# 03-PeripheralPart-V2_3.net
KiCad netlist of a schematic drawn in Altium Designer
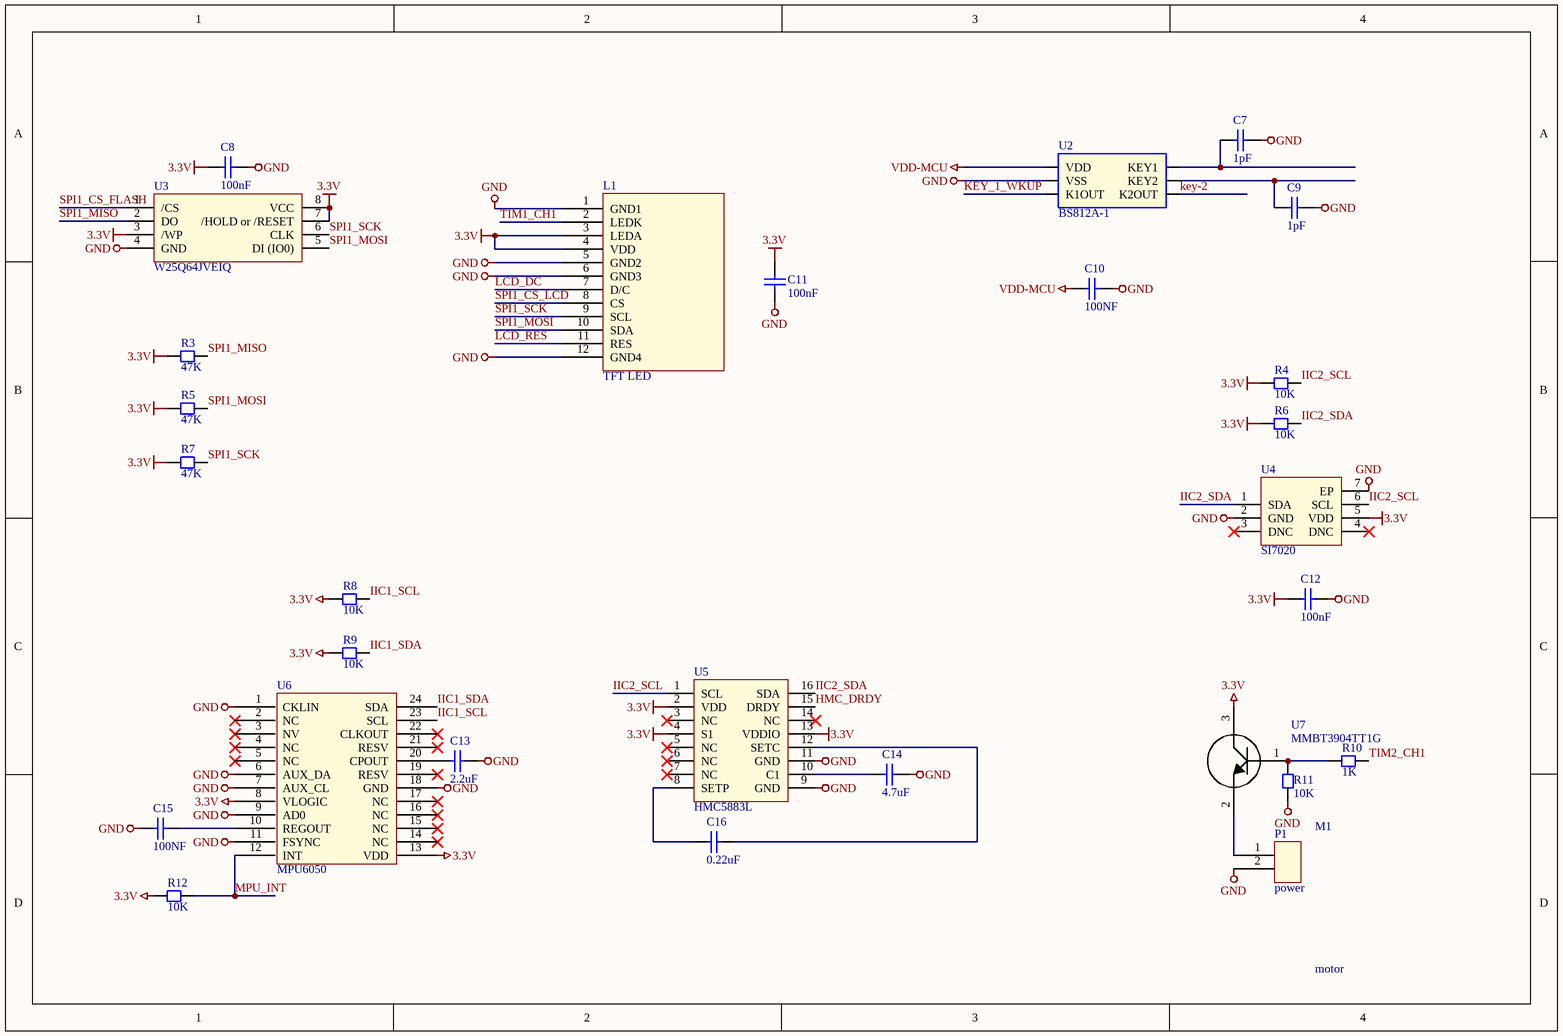
[diagram p0: 03-PeripheralPart-V2.3.SchDoc]

(export (version "E")
  (design (tool "Eeschema 10.0.6"))
  (components
    (comp (ref "C7")
      (value "1pF")
      (footprint "CC1005-0402")
      (description "贴片电容")
      (libsource (lib "tianxiaohua_Schlib") (part "Chip capacitor"))
    )
    (comp (ref "C8")
      (value "100nF")
      (footprint "CC1005-0402")
      (description "贴片电容")
      (libsource (lib "tianxiaohua_Schlib") (part "Chip capacitor"))
    )
    (comp (ref "C9")
      (value "1pF")
      (footprint "CC1005-0402")
      (description "贴片电容")
      (libsource (lib "tianxiaohua_Schlib") (part "Chip capacitor"))
    )
    (comp (ref "C10")
      (value "100NF")
      (footprint "CC1005-0402")
      (description "贴片电容")
      (libsource (lib "tianxiaohua_Schlib") (part "Chip capacitor"))
    )
    (comp (ref "C11")
      (value "100nF")
      (footprint "CC1005-0402")
      (description "贴片电容")
      (libsource (lib "tianxiaohua_Schlib") (part "Chip capacitor"))
    )
    (comp (ref "C12")
      (value "100nF")
      (footprint "CC1005-0402")
      (description "贴片电容")
      (libsource (lib "tianxiaohua_Schlib") (part "Chip capacitor"))
    )
    (comp (ref "C13")
      (value "2.2uF")
      (footprint "CC1005-0402")
      (description "贴片电容")
      (libsource (lib "tianxiaohua_Schlib") (part "Chip capacitor"))
    )
    (comp (ref "C14")
      (value "4.7uF")
      (footprint "CC1005-0402")
      (description "贴片电容")
      (libsource (lib "tianxiaohua_Schlib") (part "Chip capacitor"))
    )
    (comp (ref "C15")
      (value "100NF")
      (footprint "CC1005-0402")
      (description "贴片电容")
      (libsource (lib "tianxiaohua_Schlib") (part "Chip capacitor"))
    )
    (comp (ref "C16")
      (value "0.22uF")
      (footprint "CC1005-0402")
      (description "贴片电容")
      (libsource (lib "tianxiaohua_Schlib") (part "Chip capacitor"))
    )
    (comp (ref "L1")
      (value "TFT LED")
      (footprint "LCD-1.3-(2)")
      (description "1.3寸显示屏幕")
      (libsource (lib "tianxiaohua_Schlib") (part "LCD-IPSscreen-1.3"))
    )
    (comp (ref "M1")
      (value "motor")
      (footprint "motor")
      (description "震动马达")
      (libsource (lib "tianxiaohua_Schlib") (part "motor"))
    )
    (comp (ref "P1")
      (value "power")
      (footprint "POWER-3.7V")
      (libsource (lib "tianxiaohua_Schlib") (part "power"))
    )
    (comp (ref "R3")
      (value "47K")
      (footprint "CR1005-0402")
      (description "贴片电阻")
      (libsource (lib "tianxiaohua_Schlib") (part "Chip resistor"))
    )
    (comp (ref "R4")
      (value "10K")
      (footprint "CR1005-0402")
      (description "贴片电阻")
      (libsource (lib "tianxiaohua_Schlib") (part "Chip resistor"))
    )
    (comp (ref "R5")
      (value "47K")
      (footprint "CR1005-0402")
      (description "贴片电阻")
      (libsource (lib "tianxiaohua_Schlib") (part "Chip resistor"))
    )
    (comp (ref "R6")
      (value "10K")
      (footprint "CR1005-0402")
      (description "贴片电阻")
      (libsource (lib "tianxiaohua_Schlib") (part "Chip resistor"))
    )
    (comp (ref "R7")
      (value "47K")
      (footprint "CR1005-0402")
      (description "贴片电阻")
      (libsource (lib "tianxiaohua_Schlib") (part "Chip resistor"))
    )
    (comp (ref "R8")
      (value "10K")
      (footprint "CR1005-0402")
      (description "贴片电阻")
      (libsource (lib "tianxiaohua_Schlib") (part "Chip resistor"))
    )
    (comp (ref "R9")
      (value "10K")
      (footprint "CR1005-0402")
      (description "贴片电阻")
      (libsource (lib "tianxiaohua_Schlib") (part "Chip resistor"))
    )
    (comp (ref "R10")
      (value "1K")
      (footprint "CR1005-0402")
      (description "贴片电阻")
      (libsource (lib "tianxiaohua_Schlib") (part "Chip resistor"))
    )
    (comp (ref "R11")
      (value "10K")
      (footprint "CR1005-0402")
      (description "贴片电阻")
      (libsource (lib "") (part "Chip resistor_1"))
    )
    (comp (ref "R12")
      (value "10K")
      (footprint "CR1005-0402")
      (description "贴片电阻")
      (libsource (lib "tianxiaohua_Schlib") (part "Chip resistor"))
    )
    (comp (ref "U2")
      (value "BS812A-1")
      (footprint "SOT23-6")
      (description "触摸按键 两路 SOP23-6封装极简电路")
      (libsource (lib "tianxiaohua_Schlib") (part "BS812A-1"))
    )
    (comp (ref "U3")
      (value "W25Q64JVEIQ")
      (footprint "WSON-8_L8.0-W6.10-P1.27-TL-EP")
      (description "FLASH")
      (libsource (lib "tianxiaohua_Schlib") (part "W25Q256JVEIQ"))
    )
    (comp (ref "U4")
      (value "SI7020")
      (footprint "DFN-6")
      (description "温湿度传感器芯片")
      (libsource (lib "tianxiaohua_Schlib") (part "SI7020"))
    )
    (comp (ref "U5")
      (value "HMC5883L")
      (footprint "LPCC-16_L3.0-W3.0-P0.50-BL")
      (description "三轴罗盘")
      (libsource (lib "tianxiaohua_Schlib") (part "HMC5883L"))
    )
    (comp (ref "U6")
      (value "MPU6050")
      (footprint "QFN24 - duplicate")
      (description "陀螺仪")
      (libsource (lib "tianxiaohua_Schlib") (part "MPU6050"))
    )
    (comp (ref "U7")
      (value "MMBT3904TT1G")
      (footprint "SOT-416")
      (description "NPN 电流 - 集电极（Ic）（最大值）：200mA 电压 - 集射极击穿（最大值）：40V SOT-23-3")
      (libsource (lib "tianxiaohua_Schlib") (part "MMBT3904TT1G"))
    )
  )
  (nets
    (net (code "1") (name "/HMC_DRDY") (class "Default")
      (node (ref "U5") (pin "15") (pinfunction "DRDY_15") (pintype "passive"))
    )
    (net (code "2") (name "/IIC1_SCL") (class "Default")
      (node (ref "R8") (pin "1") (pinfunction "1_1") (pintype "passive"))
      (node (ref "U6") (pin "23") (pinfunction "SCL_23") (pintype "passive"))
    )
    (net (code "3") (name "/IIC1_SDA") (class "Default")
      (node (ref "R9") (pin "1") (pinfunction "1_1") (pintype "passive"))
      (node (ref "U6") (pin "24") (pinfunction "SDA_24") (pintype "passive"))
    )
    (net (code "4") (name "/IIC2_SCL") (class "Default")
      (node (ref "R4") (pin "1") (pinfunction "1_1") (pintype "passive"))
      (node (ref "U4") (pin "6") (pinfunction "SCL_6") (pintype "passive"))
      (node (ref "U5") (pin "1") (pinfunction "SCL_1") (pintype "passive"))
    )
    (net (code "5") (name "/IIC2_SDA") (class "Default")
      (node (ref "R6") (pin "1") (pinfunction "1_1") (pintype "passive"))
      (node (ref "U4") (pin "1") (pinfunction "SDA_1") (pintype "passive"))
      (node (ref "U5") (pin "16") (pinfunction "SDA_16") (pintype "passive"))
    )
    (net (code "6") (name "/KEY_1_WKUP") (class "Default")
      (node (ref "U2") (pin "3") (pinfunction "K1OUT_3") (pintype "passive"))
    )
    (net (code "7") (name "/LCD_DC") (class "Default")
      (node (ref "L1") (pin "7") (pinfunction "D/C_7") (pintype "passive"))
    )
    (net (code "8") (name "/LCD_RES") (class "Default")
      (node (ref "L1") (pin "11") (pinfunction "RES_11") (pintype "passive"))
    )
    (net (code "9") (name "/MPU_INT") (class "Default")
      (node (ref "R12") (pin "1") (pinfunction "1_1") (pintype "passive"))
      (node (ref "U6") (pin "12") (pinfunction "INT_12") (pintype "passive"))
    )
    (net (code "10") (name "/SPI1_CS_FLASH") (class "Default")
      (node (ref "U3") (pin "1") (pinfunction "/CS_1") (pintype "passive"))
    )
    (net (code "11") (name "/SPI1_CS_LCD") (class "Default")
      (node (ref "L1") (pin "8") (pinfunction "CS_8") (pintype "passive"))
    )
    (net (code "12") (name "/SPI1_MISO") (class "Default")
      (node (ref "R3") (pin "1") (pinfunction "1_1") (pintype "passive"))
      (node (ref "U3") (pin "2") (pinfunction "DO_2") (pintype "passive"))
    )
    (net (code "13") (name "/SPI1_MOSI") (class "Default")
      (node (ref "L1") (pin "10") (pinfunction "SDA_10") (pintype "passive"))
      (node (ref "R5") (pin "1") (pinfunction "1_1") (pintype "passive"))
      (node (ref "U3") (pin "5") (pinfunction "DI_(IO0)_5") (pintype "passive"))
    )
    (net (code "14") (name "/SPI1_SCK") (class "Default")
      (node (ref "L1") (pin "9") (pinfunction "SCL_9") (pintype "passive"))
      (node (ref "R7") (pin "1") (pinfunction "1_1") (pintype "passive"))
      (node (ref "U3") (pin "6") (pinfunction "CLK_6") (pintype "passive"))
    )
    (net (code "15") (name "/TIM1_CH1") (class "Default")
      (node (ref "L1") (pin "2") (pinfunction "LEDK_2") (pintype "passive"))
    )
    (net (code "16") (name "/TIM2_CH1") (class "Default")
      (node (ref "R10") (pin "1") (pinfunction "1_1") (pintype "passive"))
    )
    (net (code "17") (name "/key-2") (class "Default")
      (node (ref "U2") (pin "4") (pinfunction "K2OUT_4") (pintype "passive"))
    )
    (net (code "18") (name "3.3V") (class "Default")
      (node (ref "C11") (pin "1") (pinfunction "1_1") (pintype "passive"))
      (node (ref "C12") (pin "1") (pinfunction "1_1") (pintype "passive"))
      (node (ref "C8") (pin "1") (pinfunction "1_1") (pintype "passive"))
      (node (ref "L1") (pin "3") (pinfunction "LEDA_3") (pintype "passive"))
      (node (ref "L1") (pin "4") (pinfunction "VDD_4") (pintype "passive"))
      (node (ref "R12") (pin "2") (pinfunction "2_2") (pintype "passive"))
      (node (ref "R3") (pin "2") (pinfunction "2_2") (pintype "passive"))
      (node (ref "R4") (pin "2") (pinfunction "2_2") (pintype "passive"))
      (node (ref "R5") (pin "2") (pinfunction "2_2") (pintype "passive"))
      (node (ref "R6") (pin "2") (pinfunction "2_2") (pintype "passive"))
      (node (ref "R7") (pin "2") (pinfunction "2_2") (pintype "passive"))
      (node (ref "R8") (pin "2") (pinfunction "2_2") (pintype "passive"))
      (node (ref "R9") (pin "2") (pinfunction "2_2") (pintype "passive"))
      (node (ref "U3") (pin "3") (pinfunction "/WP_3") (pintype "passive"))
      (node (ref "U3") (pin "7") (pinfunction "/HOLD_or_/RESET_7") (pintype "passive"))
      (node (ref "U3") (pin "8") (pinfunction "VCC_8") (pintype "passive"))
      (node (ref "U4") (pin "5") (pinfunction "VDD_5") (pintype "passive"))
      (node (ref "U5") (pin "13") (pinfunction "VDDIO_13") (pintype "passive"))
      (node (ref "U5") (pin "2") (pinfunction "VDD_2") (pintype "passive"))
      (node (ref "U5") (pin "4") (pinfunction "S1_4") (pintype "passive"))
      (node (ref "U6") (pin "13") (pinfunction "VDD_13") (pintype "passive"))
      (node (ref "U6") (pin "8") (pinfunction "VLOGIC_8") (pintype "passive"))
      (node (ref "U7") (pin "3") (pinfunction "3_3") (pintype "passive"))
    )
    (net (code "19") (name "GND") (class "Default")
      (node (ref "C10") (pin "1") (pinfunction "1_1") (pintype "passive"))
      (node (ref "C11") (pin "2") (pinfunction "2_2") (pintype "passive"))
      (node (ref "C12") (pin "2") (pinfunction "2_2") (pintype "passive"))
      (node (ref "C13") (pin "2") (pinfunction "2_2") (pintype "passive"))
      (node (ref "C14") (pin "2") (pinfunction "2_2") (pintype "passive"))
      (node (ref "C15") (pin "1") (pinfunction "1_1") (pintype "passive"))
      (node (ref "C7") (pin "2") (pinfunction "2_2") (pintype "passive"))
      (node (ref "C8") (pin "2") (pinfunction "2_2") (pintype "passive"))
      (node (ref "C9") (pin "2") (pinfunction "2_2") (pintype "passive"))
      (node (ref "L1") (pin "1") (pinfunction "GND1_1") (pintype "passive"))
      (node (ref "L1") (pin "12") (pinfunction "GND4_12") (pintype "passive"))
      (node (ref "L1") (pin "5") (pinfunction "GND2_5") (pintype "passive"))
      (node (ref "L1") (pin "6") (pinfunction "GND3_6") (pintype "passive"))
      (node (ref "P1") (pin "2") (pinfunction "2_2") (pintype "passive"))
      (node (ref "R11") (pin "2") (pinfunction "2_2") (pintype "passive"))
      (node (ref "U2") (pin "2") (pinfunction "VSS_2") (pintype "passive"))
      (node (ref "U3") (pin "4") (pinfunction "GND_4") (pintype "passive"))
      (node (ref "U4") (pin "2") (pinfunction "GND_2") (pintype "passive"))
      (node (ref "U4") (pin "7") (pinfunction "EP_7") (pintype "passive"))
      (node (ref "U5") (pin "11") (pinfunction "GND_11") (pintype "passive"))
      (node (ref "U5") (pin "9") (pinfunction "GND_9") (pintype "passive"))
      (node (ref "U6") (pin "1") (pinfunction "CKLIN_1") (pintype "passive"))
      (node (ref "U6") (pin "11") (pinfunction "FSYNC_11") (pintype "passive"))
      (node (ref "U6") (pin "18") (pinfunction "GND_18") (pintype "passive"))
      (node (ref "U6") (pin "6") (pinfunction "AUX_DA_6") (pintype "passive"))
      (node (ref "U6") (pin "7") (pinfunction "AUX_CL_7") (pintype "passive"))
      (node (ref "U6") (pin "9") (pinfunction "AD0_9") (pintype "passive"))
    )
    (net (code "20") (name "Net-(P1-Pad1)") (class "Default")
      (node (ref "P1") (pin "1") (pinfunction "1_1") (pintype "passive"))
      (node (ref "U7") (pin "2") (pinfunction "2_2") (pintype "passive"))
    )
    (net (code "21") (name "Net-(R10-Pad2)") (class "Default")
      (node (ref "R10") (pin "2") (pinfunction "2_2") (pintype "passive"))
      (node (ref "R11") (pin "1") (pinfunction "1_1") (pintype "passive"))
      (node (ref "U7") (pin "1") (pinfunction "1_1") (pintype "passive"))
    )
    (net (code "22") (name "Net-(U2-KEY1)") (class "Default")
      (node (ref "C7") (pin "1") (pinfunction "1_1") (pintype "passive"))
      (node (ref "U2") (pin "6") (pinfunction "KEY1_6") (pintype "passive"))
    )
    (net (code "23") (name "Net-(U2-KEY2)") (class "Default")
      (node (ref "C9") (pin "1") (pinfunction "1_1") (pintype "passive"))
      (node (ref "U2") (pin "5") (pinfunction "KEY2_5") (pintype "passive"))
    )
    (net (code "24") (name "Net-(U5-C1)") (class "Default")
      (node (ref "C14") (pin "1") (pinfunction "1_1") (pintype "passive"))
      (node (ref "U5") (pin "10") (pinfunction "C1_10") (pintype "passive"))
    )
    (net (code "25") (name "Net-(U5-SETC)") (class "Default")
      (node (ref "C16") (pin "2") (pinfunction "2_2") (pintype "passive"))
      (node (ref "U5") (pin "12") (pinfunction "SETC_12") (pintype "passive"))
    )
    (net (code "26") (name "Net-(U5-SETP)") (class "Default")
      (node (ref "C16") (pin "1") (pinfunction "1_1") (pintype "passive"))
      (node (ref "U5") (pin "8") (pinfunction "SETP_8") (pintype "passive"))
    )
    (net (code "27") (name "Net-(U6-CPOUT)") (class "Default")
      (node (ref "C13") (pin "1") (pinfunction "1_1") (pintype "passive"))
      (node (ref "U6") (pin "20") (pinfunction "CPOUT_20") (pintype "passive"))
    )
    (net (code "28") (name "Net-(U6-REGOUT)") (class "Default")
      (node (ref "C15") (pin "2") (pinfunction "2_2") (pintype "passive"))
      (node (ref "U6") (pin "10") (pinfunction "REGOUT_10") (pintype "passive"))
    )
    (net (code "29") (name "VDD-MCU") (class "Default")
      (node (ref "C10") (pin "2") (pinfunction "2_2") (pintype "passive"))
      (node (ref "U2") (pin "1") (pinfunction "VDD_1") (pintype "passive"))
    )
    (net (code "30") (name "unconnected-(U4-DNC-Pad3)") (class "Default")
      (node (ref "U4") (pin "3") (pinfunction "DNC_3") (pintype "passive+no_connect"))
    )
    (net (code "31") (name "unconnected-(U4-DNC-Pad4)") (class "Default")
      (node (ref "U4") (pin "4") (pinfunction "DNC_4") (pintype "passive+no_connect"))
    )
    (net (code "32") (name "unconnected-(U5-NC-Pad3)") (class "Default")
      (node (ref "U5") (pin "3") (pinfunction "NC_3") (pintype "passive+no_connect"))
    )
    (net (code "33") (name "unconnected-(U5-NC-Pad5)") (class "Default")
      (node (ref "U5") (pin "5") (pinfunction "NC_5") (pintype "passive+no_connect"))
    )
    (net (code "34") (name "unconnected-(U5-NC-Pad6)") (class "Default")
      (node (ref "U5") (pin "6") (pinfunction "NC_6") (pintype "passive+no_connect"))
    )
    (net (code "35") (name "unconnected-(U5-NC-Pad7)") (class "Default")
      (node (ref "U5") (pin "7") (pinfunction "NC_7") (pintype "passive+no_connect"))
    )
    (net (code "36") (name "unconnected-(U5-NC-Pad14)") (class "Default")
      (node (ref "U5") (pin "14") (pinfunction "NC_14") (pintype "passive+no_connect"))
    )
    (net (code "37") (name "unconnected-(U6-CLKOUT-Pad22)") (class "Default")
      (node (ref "U6") (pin "22") (pinfunction "CLKOUT_22") (pintype "passive+no_connect"))
    )
    (net (code "38") (name "unconnected-(U6-NC-Pad2)") (class "Default")
      (node (ref "U6") (pin "2") (pinfunction "NC_2") (pintype "passive+no_connect"))
    )
    (net (code "39") (name "unconnected-(U6-NC-Pad4)") (class "Default")
      (node (ref "U6") (pin "4") (pinfunction "NC_4") (pintype "passive+no_connect"))
    )
    (net (code "40") (name "unconnected-(U6-NC-Pad5)") (class "Default")
      (node (ref "U6") (pin "5") (pinfunction "NC_5") (pintype "passive+no_connect"))
    )
    (net (code "41") (name "unconnected-(U6-NC-Pad14)") (class "Default")
      (node (ref "U6") (pin "14") (pinfunction "NC_14") (pintype "passive+no_connect"))
    )
    (net (code "42") (name "unconnected-(U6-NC-Pad15)") (class "Default")
      (node (ref "U6") (pin "15") (pinfunction "NC_15") (pintype "passive+no_connect"))
    )
    (net (code "43") (name "unconnected-(U6-NC-Pad16)") (class "Default")
      (node (ref "U6") (pin "16") (pinfunction "NC_16") (pintype "passive+no_connect"))
    )
    (net (code "44") (name "unconnected-(U6-NC-Pad17)") (class "Default")
      (node (ref "U6") (pin "17") (pinfunction "NC_17") (pintype "passive+no_connect"))
    )
    (net (code "45") (name "unconnected-(U6-NV-Pad3)") (class "Default")
      (node (ref "U6") (pin "3") (pinfunction "NV_3") (pintype "passive+no_connect"))
    )
    (net (code "46") (name "unconnected-(U6-RESV-Pad19)") (class "Default")
      (node (ref "U6") (pin "19") (pinfunction "RESV_19") (pintype "passive+no_connect"))
    )
    (net (code "47") (name "unconnected-(U6-RESV-Pad21)") (class "Default")
      (node (ref "U6") (pin "21") (pinfunction "RESV_21") (pintype "passive+no_connect"))
    )
  )
)
